# RFID_Breakout.net
KiCad netlist of a schematic drawn in EAGLE
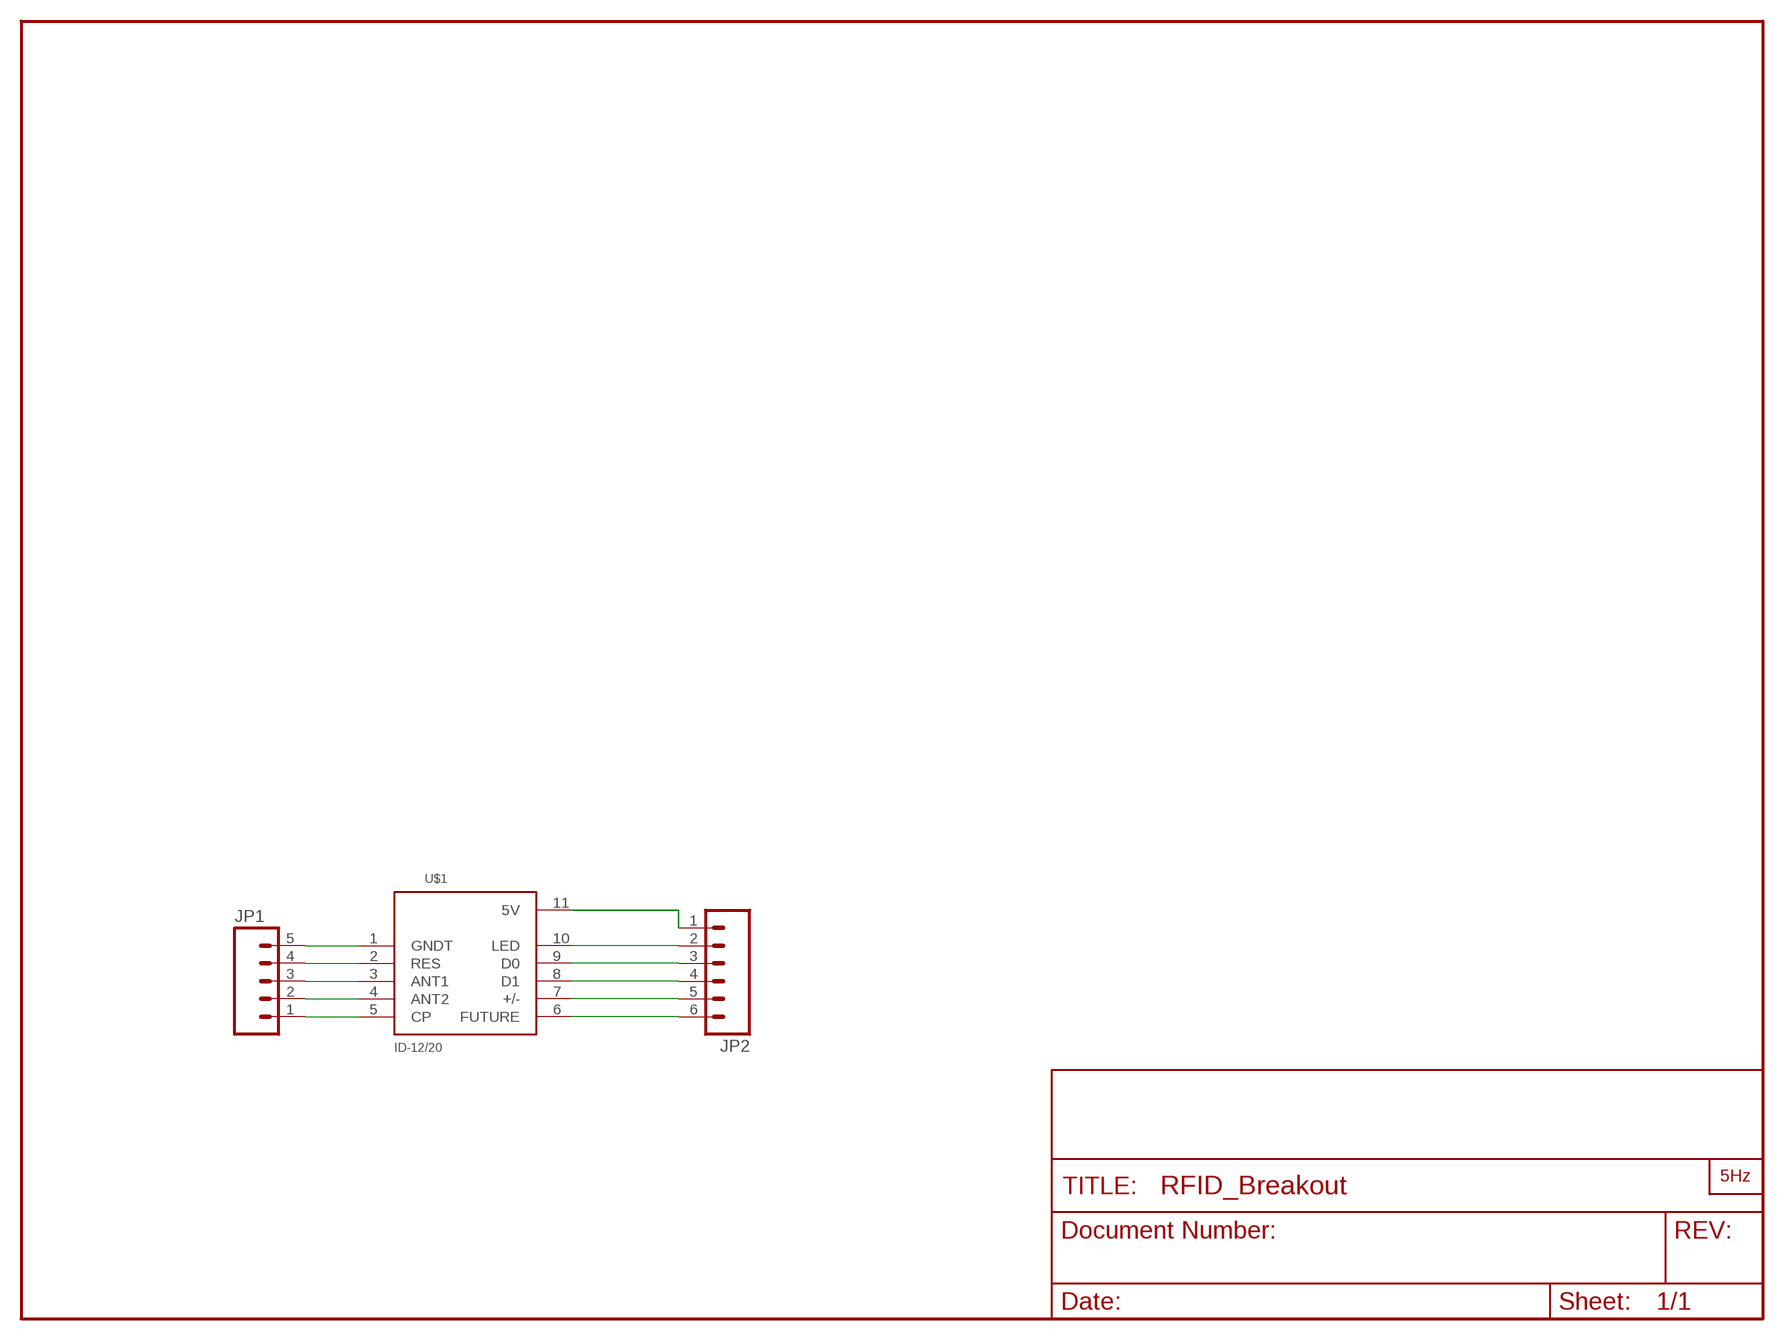
[diagram p0: schematic, sheet 1]

(export (version "E")
  (design (tool "Eeschema 10.0.6"))
  (components
    (comp (ref "JP1")
      (value "M05PTH")
      (footprint "eagle-import:1X05")
      (libsource (lib "eagle-import") (part "M05PTH"))
    )
    (comp (ref "JP2")
      (value "M06SIP")
      (footprint "eagle-import:1X06")
      (libsource (lib "eagle-import") (part "M06SIP"))
    )
    (comp (ref "U$1")
      (value "ID-12/20")
      (footprint "eagle-import:ID-12")
      (libsource (lib "eagle-import") (part "ID-12/20"))
    )
    (comp (ref "U$2")
      (value "LOGO2_SILK5MM")
      (footprint "eagle-import:LOGO2_5MM")
      (libsource (lib "eagle-import") (part "LOGO2_SILK5MM"))
    )
  )
  (nets
    (net (code "1") (name "Net-(U$1-+{slash}-)") (class "Default")
      (node (ref "JP2") (pin "5") (pinfunction "5_5") (pintype "passive"))
      (node (ref "U$1") (pin "7") (pinfunction "+/-_7") (pintype "bidirectional"))
    )
    (net (code "2") (name "Net-(U$1-5V)") (class "Default")
      (node (ref "JP2") (pin "1") (pinfunction "1_1") (pintype "passive"))
      (node (ref "U$1") (pin "11") (pinfunction "5V_11") (pintype "bidirectional"))
    )
    (net (code "3") (name "Net-(U$1-ANT1)") (class "Default")
      (node (ref "JP1") (pin "3") (pinfunction "3_3") (pintype "passive"))
      (node (ref "U$1") (pin "3") (pinfunction "ANT1_3") (pintype "bidirectional"))
    )
    (net (code "4") (name "Net-(U$1-ANT2)") (class "Default")
      (node (ref "JP1") (pin "2") (pinfunction "2_2") (pintype "passive"))
      (node (ref "U$1") (pin "4") (pinfunction "ANT2_4") (pintype "bidirectional"))
    )
    (net (code "5") (name "Net-(U$1-CP)") (class "Default")
      (node (ref "JP1") (pin "1") (pinfunction "1_1") (pintype "passive"))
      (node (ref "U$1") (pin "5") (pinfunction "CP_5") (pintype "bidirectional"))
    )
    (net (code "6") (name "Net-(U$1-D0)") (class "Default")
      (node (ref "JP2") (pin "3") (pinfunction "3_3") (pintype "passive"))
      (node (ref "U$1") (pin "9") (pinfunction "D0_9") (pintype "bidirectional"))
    )
    (net (code "7") (name "Net-(U$1-D1)") (class "Default")
      (node (ref "JP2") (pin "4") (pinfunction "4_4") (pintype "passive"))
      (node (ref "U$1") (pin "8") (pinfunction "D1_8") (pintype "bidirectional"))
    )
    (net (code "8") (name "Net-(U$1-FUTURE)") (class "Default")
      (node (ref "JP2") (pin "6") (pinfunction "6_6") (pintype "passive"))
      (node (ref "U$1") (pin "6") (pinfunction "FUTURE_6") (pintype "bidirectional"))
    )
    (net (code "9") (name "Net-(U$1-GNDT)") (class "Default")
      (node (ref "JP1") (pin "5") (pinfunction "5_5") (pintype "passive"))
      (node (ref "U$1") (pin "1") (pinfunction "GNDT_1") (pintype "bidirectional"))
    )
    (net (code "10") (name "Net-(U$1-LED)") (class "Default")
      (node (ref "JP2") (pin "2") (pinfunction "2_2") (pintype "passive"))
      (node (ref "U$1") (pin "10") (pinfunction "LED_10") (pintype "bidirectional"))
    )
    (net (code "11") (name "Net-(U$1-RES)") (class "Default")
      (node (ref "JP1") (pin "4") (pinfunction "4_4") (pintype "passive"))
      (node (ref "U$1") (pin "2") (pinfunction "RES_2") (pintype "bidirectional"))
    )
  )
)
